# leduino.net
KiCad netlist of a schematic drawn in EAGLE
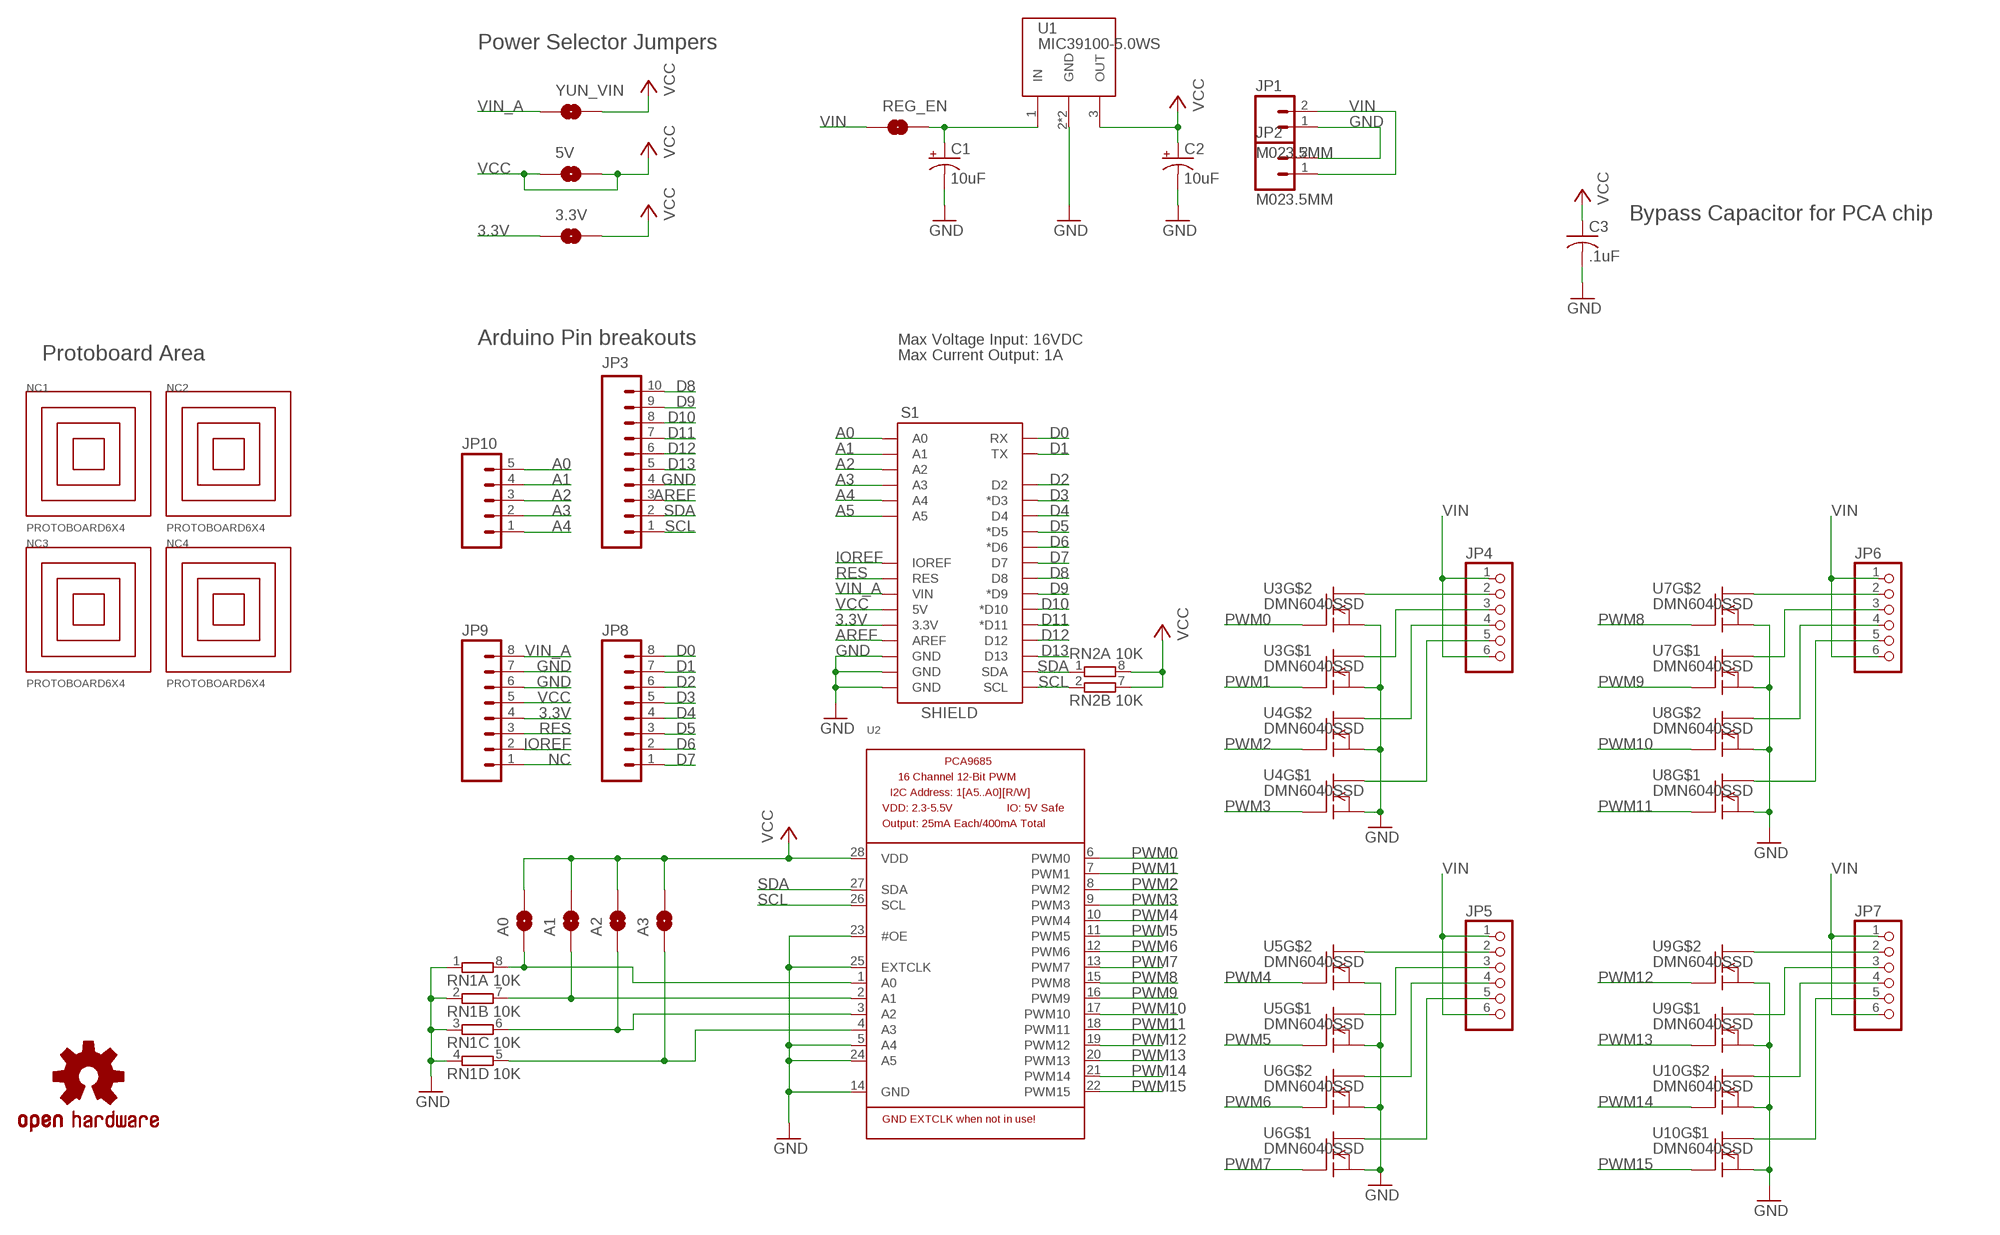
[diagram p0: schematic, sheet 1]

(export (version "E")
  (design (tool "Eeschema 10.0.6"))
  (components
    (comp (ref "3.3V")
      (value "SOLDERJUMPERNO")
      (footprint "eagle-import:SJ_2S-NO")
      (libsource (lib "eagle-import") (part "SOLDERJUMPERNO"))
    )
    (comp (ref "5V")
      (value "SOLDERJUMPERNO")
      (footprint "eagle-import:SJ_2S-NO")
      (libsource (lib "eagle-import") (part "SOLDERJUMPERNO"))
    )
    (comp (ref "A0")
      (value "SOLDERJUMPERNO")
      (footprint "eagle-import:SJ_2S-NO")
      (libsource (lib "eagle-import") (part "SOLDERJUMPERNO"))
    )
    (comp (ref "A1")
      (value "SOLDERJUMPERNO")
      (footprint "eagle-import:SJ_2S-NO")
      (libsource (lib "eagle-import") (part "SOLDERJUMPERNO"))
    )
    (comp (ref "A2")
      (value "SOLDERJUMPERNO")
      (footprint "eagle-import:SJ_2S-NO")
      (libsource (lib "eagle-import") (part "SOLDERJUMPERNO"))
    )
    (comp (ref "A3")
      (value "SOLDERJUMPERNO")
      (footprint "eagle-import:SJ_2S-NO")
      (libsource (lib "eagle-import") (part "SOLDERJUMPERNO"))
    )
    (comp (ref "C1")
      (value "10uF")
      (footprint "eagle-import:EIA3216")
      (libsource (lib "eagle-import") (part "CAP_POL1206"))
    )
    (comp (ref "C2")
      (value "10uF")
      (footprint "eagle-import:EIA3216")
      (libsource (lib "eagle-import") (part "CAP_POL1206"))
    )
    (comp (ref "C3")
      (value ".1uF")
      (footprint "eagle-import:C0805")
      (libsource (lib "eagle-import") (part "C-USC0805"))
    )
    (comp (ref "JP1")
      (value "M023.5MM")
      (footprint "eagle-import:SCREWTERMINAL-3.5MM-2")
      (libsource (lib "eagle-import") (part "M023.5MM"))
    )
    (comp (ref "JP2")
      (value "M023.5MM")
      (footprint "eagle-import:SCREWTERMINAL-3.5MM-2")
      (libsource (lib "eagle-import") (part "M023.5MM"))
    )
    (comp (ref "JP3")
      (value "M10NO_SILK_PTH_FEMALE")
      (footprint "eagle-import:1X10_NO_SILK")
      (libsource (lib "eagle-import") (part "M10NO_SILK_PTH_FEMALE"))
    )
    (comp (ref "JP4")
      (value "PINHD-1X63.5MM-RA")
      (footprint "eagle-import:1X06-3.5M-RA")
      (libsource (lib "eagle-import") (part "PINHD-1X63.5MM-RA"))
    )
    (comp (ref "JP5")
      (value "PINHD-1X63.5MM-RA")
      (footprint "eagle-import:1X06-3.5M-RA")
      (libsource (lib "eagle-import") (part "PINHD-1X63.5MM-RA"))
    )
    (comp (ref "JP6")
      (value "PINHD-1X63.5MM-RA")
      (footprint "eagle-import:1X06-3.5M-RA")
      (libsource (lib "eagle-import") (part "PINHD-1X63.5MM-RA"))
    )
    (comp (ref "JP7")
      (value "PINHD-1X63.5MM-RA")
      (footprint "eagle-import:1X06-3.5M-RA")
      (libsource (lib "eagle-import") (part "PINHD-1X63.5MM-RA"))
    )
    (comp (ref "JP8")
      (value "M08NO_SILK_FEMALE_PTH")
      (footprint "eagle-import:1X08_NO_SILK")
      (libsource (lib "eagle-import") (part "M08NO_SILK_FEMALE_PTH"))
    )
    (comp (ref "JP9")
      (value "M08NO_SILK_FEMALE_PTH")
      (footprint "eagle-import:1X08_NO_SILK")
      (libsource (lib "eagle-import") (part "M08NO_SILK_FEMALE_PTH"))
    )
    (comp (ref "JP10")
      (value "M05NO_SILK")
      (footprint "eagle-import:1X05_NO_SILK")
      (libsource (lib "eagle-import") (part "M05NO_SILK"))
    )
    (comp (ref "NC1")
      (value "PROTOBOARD6X4")
      (footprint "eagle-import:PROTOBOARD_6X4")
      (libsource (lib "eagle-import") (part "PROTOBOARD6X4"))
    )
    (comp (ref "NC2")
      (value "PROTOBOARD6X4")
      (footprint "eagle-import:PROTOBOARD_6X4")
      (libsource (lib "eagle-import") (part "PROTOBOARD6X4"))
    )
    (comp (ref "NC3")
      (value "PROTOBOARD6X4")
      (footprint "eagle-import:PROTOBOARD_6X4")
      (libsource (lib "eagle-import") (part "PROTOBOARD6X4"))
    )
    (comp (ref "NC4")
      (value "PROTOBOARD6X4")
      (footprint "eagle-import:PROTOBOARD_6X4")
      (libsource (lib "eagle-import") (part "PROTOBOARD6X4"))
    )
    (comp (ref "REG_EN")
      (value "SOLDERJUMPERNO")
      (footprint "eagle-import:SJ_2S-NO")
      (libsource (lib "eagle-import") (part "SOLDERJUMPERNO"))
    )
    (comp (ref "RN1")
      (value "10K")
      (footprint "eagle-import:EXB38V")
      (libsource (lib "eagle-import") (part "4R-NEXB38V"))
    )
    (comp (ref "RN2")
      (value "10K")
      (footprint "eagle-import:EXB38V")
      (libsource (lib "eagle-import") (part "4R-NEXB38V"))
    )
    (comp (ref "S1")
      (value "SHIELD")
      (footprint "eagle-import:ARDUINOR3")
      (libsource (lib "eagle-import") (part "ARDUINO_R3_SHIELD"))
    )
    (comp (ref "U$6")
      (value "OSHW-LOGOM")
      (footprint "eagle-import:OSHW-LOGO-M")
      (libsource (lib "eagle-import") (part "OSHW-LOGOM"))
    )
    (comp (ref "U1")
      (value "MIC39100-5.0WS")
      (footprint "eagle-import:SOT223")
      (libsource (lib "eagle-import") (part "MIC39100"))
    )
    (comp (ref "U2")
      (value "PCA9685")
      (footprint "eagle-import:TSSOP28")
      (libsource (lib "eagle-import") (part "PCA9685"))
    )
    (comp (ref "U3")
      (value "DMN6040SSD")
      (footprint "eagle-import:SO8")
      (libsource (lib "eagle-import") (part "DMN6040SSD"))
    )
    (comp (ref "U4")
      (value "DMN6040SSD")
      (footprint "eagle-import:SO8")
      (libsource (lib "eagle-import") (part "DMN6040SSD"))
    )
    (comp (ref "U5")
      (value "DMN6040SSD")
      (footprint "eagle-import:SO8")
      (libsource (lib "eagle-import") (part "DMN6040SSD"))
    )
    (comp (ref "U6")
      (value "DMN6040SSD")
      (footprint "eagle-import:SO8")
      (libsource (lib "eagle-import") (part "DMN6040SSD"))
    )
    (comp (ref "U7")
      (value "DMN6040SSD")
      (footprint "eagle-import:SO8")
      (libsource (lib "eagle-import") (part "DMN6040SSD"))
    )
    (comp (ref "U8")
      (value "DMN6040SSD")
      (footprint "eagle-import:SO8")
      (libsource (lib "eagle-import") (part "DMN6040SSD"))
    )
    (comp (ref "U9")
      (value "DMN6040SSD")
      (footprint "eagle-import:SO8")
      (libsource (lib "eagle-import") (part "DMN6040SSD"))
    )
    (comp (ref "U10")
      (value "DMN6040SSD")
      (footprint "eagle-import:SO8")
      (libsource (lib "eagle-import") (part "DMN6040SSD"))
    )
    (comp (ref "YUN_VIN")
      (value "SOLDERJUMPERNO")
      (footprint "eagle-import:SJ_2S-NO")
      (libsource (lib "eagle-import") (part "SOLDERJUMPERNO"))
    )
  )
  (nets
    (net (code "1") (name "/3.3V") (class "Default")
      (node (ref "3.3V") (pin "1") (pinfunction "1_1") (pintype "passive"))
      (node (ref "JP9") (pin "4") (pinfunction "4_4") (pintype "passive"))
      (node (ref "S1") (pin "3V") (pinfunction "3.3V_3V") (pintype "bidirectional"))
    )
    (net (code "2") (name "/A0") (class "Default")
      (node (ref "JP10") (pin "5") (pinfunction "5_5") (pintype "passive"))
      (node (ref "S1") (pin "A0") (pinfunction "A0_A0") (pintype "bidirectional"))
    )
    (net (code "3") (name "/A1") (class "Default")
      (node (ref "JP10") (pin "4") (pinfunction "4_4") (pintype "passive"))
      (node (ref "S1") (pin "A1") (pinfunction "A1_A1") (pintype "bidirectional"))
    )
    (net (code "4") (name "/A2") (class "Default")
      (node (ref "JP10") (pin "3") (pinfunction "3_3") (pintype "passive"))
      (node (ref "S1") (pin "A2") (pinfunction "A2_A2") (pintype "bidirectional"))
    )
    (net (code "5") (name "/A3") (class "Default")
      (node (ref "JP10") (pin "2") (pinfunction "2_2") (pintype "passive"))
      (node (ref "S1") (pin "A3") (pinfunction "A3_A3") (pintype "bidirectional"))
    )
    (net (code "6") (name "/A4") (class "Default")
      (node (ref "JP10") (pin "1") (pinfunction "1_1") (pintype "passive"))
      (node (ref "S1") (pin "A4") (pinfunction "A4_A4") (pintype "bidirectional"))
    )
    (net (code "7") (name "/A5") (class "Default")
      (node (ref "S1") (pin "A5") (pinfunction "A5_A5") (pintype "bidirectional"))
    )
    (net (code "8") (name "/AREF") (class "Default")
      (node (ref "JP3") (pin "3") (pinfunction "3_3") (pintype "passive"))
      (node (ref "S1") (pin "AREF") (pinfunction "AREF_AREF") (pintype "bidirectional"))
    )
    (net (code "9") (name "/D0") (class "Default")
      (node (ref "JP8") (pin "8") (pinfunction "8_8") (pintype "passive"))
      (node (ref "S1") (pin "D0") (pinfunction "RX_D0") (pintype "bidirectional"))
    )
    (net (code "10") (name "/D1") (class "Default")
      (node (ref "JP8") (pin "7") (pinfunction "7_7") (pintype "passive"))
      (node (ref "S1") (pin "D1") (pinfunction "TX_D1") (pintype "bidirectional"))
    )
    (net (code "11") (name "/D2") (class "Default")
      (node (ref "JP8") (pin "6") (pinfunction "6_6") (pintype "passive"))
      (node (ref "S1") (pin "D2") (pinfunction "D2_D2") (pintype "bidirectional"))
    )
    (net (code "12") (name "/D3") (class "Default")
      (node (ref "JP8") (pin "5") (pinfunction "5_5") (pintype "passive"))
      (node (ref "S1") (pin "D3") (pinfunction "*D3_D3") (pintype "bidirectional"))
    )
    (net (code "13") (name "/D4") (class "Default")
      (node (ref "JP8") (pin "4") (pinfunction "4_4") (pintype "passive"))
      (node (ref "S1") (pin "D4") (pinfunction "D4_D4") (pintype "bidirectional"))
    )
    (net (code "14") (name "/D5") (class "Default")
      (node (ref "JP8") (pin "3") (pinfunction "3_3") (pintype "passive"))
      (node (ref "S1") (pin "D5") (pinfunction "*D5_D5") (pintype "bidirectional"))
    )
    (net (code "15") (name "/D6") (class "Default")
      (node (ref "JP8") (pin "2") (pinfunction "2_2") (pintype "passive"))
      (node (ref "S1") (pin "D6") (pinfunction "*D6_D6") (pintype "bidirectional"))
    )
    (net (code "16") (name "/D7") (class "Default")
      (node (ref "JP8") (pin "1") (pinfunction "1_1") (pintype "passive"))
      (node (ref "S1") (pin "D7") (pinfunction "D7_D7") (pintype "bidirectional"))
    )
    (net (code "17") (name "/D8") (class "Default")
      (node (ref "JP3") (pin "10") (pinfunction "10_10") (pintype "passive"))
      (node (ref "S1") (pin "D8") (pinfunction "D8_D8") (pintype "bidirectional"))
    )
    (net (code "18") (name "/D9") (class "Default")
      (node (ref "JP3") (pin "9") (pinfunction "9_9") (pintype "passive"))
      (node (ref "S1") (pin "D9") (pinfunction "*D9_D9") (pintype "bidirectional"))
    )
    (net (code "19") (name "/D10") (class "Default")
      (node (ref "JP3") (pin "8") (pinfunction "8_8") (pintype "passive"))
      (node (ref "S1") (pin "D10") (pinfunction "*D10_D10") (pintype "bidirectional"))
    )
    (net (code "20") (name "/D11") (class "Default")
      (node (ref "JP3") (pin "7") (pinfunction "7_7") (pintype "passive"))
      (node (ref "S1") (pin "D11") (pinfunction "*D11_D11") (pintype "bidirectional"))
    )
    (net (code "21") (name "/D12") (class "Default")
      (node (ref "JP3") (pin "6") (pinfunction "6_6") (pintype "passive"))
      (node (ref "S1") (pin "D12") (pinfunction "D12_D12") (pintype "bidirectional"))
    )
    (net (code "22") (name "/D13") (class "Default")
      (node (ref "JP3") (pin "5") (pinfunction "5_5") (pintype "passive"))
      (node (ref "S1") (pin "D13") (pinfunction "D13_D13") (pintype "bidirectional"))
    )
    (net (code "23") (name "/IOREF") (class "Default")
      (node (ref "JP9") (pin "2") (pinfunction "2_2") (pintype "passive"))
      (node (ref "S1") (pin "IOREF") (pinfunction "IOREF_IOREF") (pintype "bidirectional"))
    )
    (net (code "24") (name "/NC") (class "Default")
      (node (ref "JP9") (pin "1") (pinfunction "1_1") (pintype "passive"))
    )
    (net (code "25") (name "/PWM0") (class "Default")
      (node (ref "U2") (pin "6") (pinfunction "PWM0_6") (pintype "output"))
      (node (ref "U3") (pin "4") (pinfunction "G_4") (pintype "passive"))
    )
    (net (code "26") (name "/PWM1") (class "Default")
      (node (ref "U2") (pin "7") (pinfunction "PWM1_7") (pintype "output"))
      (node (ref "U3") (pin "2") (pinfunction "G_2") (pintype "passive"))
    )
    (net (code "27") (name "/PWM2") (class "Default")
      (node (ref "U2") (pin "8") (pinfunction "PWM2_8") (pintype "output"))
      (node (ref "U4") (pin "4") (pinfunction "G_4") (pintype "passive"))
    )
    (net (code "28") (name "/PWM3") (class "Default")
      (node (ref "U2") (pin "9") (pinfunction "PWM3_9") (pintype "output"))
      (node (ref "U4") (pin "2") (pinfunction "G_2") (pintype "passive"))
    )
    (net (code "29") (name "/PWM4") (class "Default")
      (node (ref "U2") (pin "10") (pinfunction "PWM4_10") (pintype "output"))
      (node (ref "U5") (pin "4") (pinfunction "G_4") (pintype "passive"))
    )
    (net (code "30") (name "/PWM5") (class "Default")
      (node (ref "U2") (pin "11") (pinfunction "PWM5_11") (pintype "output"))
      (node (ref "U5") (pin "2") (pinfunction "G_2") (pintype "passive"))
    )
    (net (code "31") (name "/PWM6") (class "Default")
      (node (ref "U2") (pin "12") (pinfunction "PWM6_12") (pintype "output"))
      (node (ref "U6") (pin "4") (pinfunction "G_4") (pintype "passive"))
    )
    (net (code "32") (name "/PWM7") (class "Default")
      (node (ref "U2") (pin "13") (pinfunction "PWM7_13") (pintype "output"))
      (node (ref "U6") (pin "2") (pinfunction "G_2") (pintype "passive"))
    )
    (net (code "33") (name "/PWM8") (class "Default")
      (node (ref "U2") (pin "15") (pinfunction "PWM8_15") (pintype "output"))
      (node (ref "U7") (pin "4") (pinfunction "G_4") (pintype "passive"))
    )
    (net (code "34") (name "/PWM9") (class "Default")
      (node (ref "U2") (pin "16") (pinfunction "PWM9_16") (pintype "output"))
      (node (ref "U7") (pin "2") (pinfunction "G_2") (pintype "passive"))
    )
    (net (code "35") (name "/PWM10") (class "Default")
      (node (ref "U2") (pin "17") (pinfunction "PWM10_17") (pintype "output"))
      (node (ref "U8") (pin "4") (pinfunction "G_4") (pintype "passive"))
    )
    (net (code "36") (name "/PWM11") (class "Default")
      (node (ref "U2") (pin "18") (pinfunction "PWM11_18") (pintype "output"))
      (node (ref "U8") (pin "2") (pinfunction "G_2") (pintype "passive"))
    )
    (net (code "37") (name "/PWM12") (class "Default")
      (node (ref "U2") (pin "19") (pinfunction "PWM12_19") (pintype "output"))
      (node (ref "U9") (pin "4") (pinfunction "G_4") (pintype "passive"))
    )
    (net (code "38") (name "/PWM13") (class "Default")
      (node (ref "U2") (pin "20") (pinfunction "PWM13_20") (pintype "output"))
      (node (ref "U9") (pin "2") (pinfunction "G_2") (pintype "passive"))
    )
    (net (code "39") (name "/PWM14") (class "Default")
      (node (ref "U10") (pin "4") (pinfunction "G_4") (pintype "passive"))
      (node (ref "U2") (pin "21") (pinfunction "PWM14_21") (pintype "output"))
    )
    (net (code "40") (name "/PWM15") (class "Default")
      (node (ref "U10") (pin "2") (pinfunction "G_2") (pintype "passive"))
      (node (ref "U2") (pin "22") (pinfunction "PWM15_22") (pintype "output"))
    )
    (net (code "41") (name "/RES") (class "Default")
      (node (ref "JP9") (pin "3") (pinfunction "3_3") (pintype "passive"))
      (node (ref "S1") (pin "RESET") (pinfunction "RES_RESET") (pintype "bidirectional"))
    )
    (net (code "42") (name "/SCL") (class "Default")
      (node (ref "JP3") (pin "1") (pinfunction "1_1") (pintype "passive"))
      (node (ref "RN2") (pin "2") (pinfunction "1_2") (pintype "passive"))
      (node (ref "S1") (pin "SCL") (pinfunction "SCL_SCL") (pintype "bidirectional"))
      (node (ref "U2") (pin "26") (pinfunction "SCL_26") (pintype "bidirectional"))
    )
    (net (code "43") (name "/SDA") (class "Default")
      (node (ref "JP3") (pin "2") (pinfunction "2_2") (pintype "passive"))
      (node (ref "RN2") (pin "1") (pinfunction "1_1") (pintype "passive"))
      (node (ref "S1") (pin "SDA") (pinfunction "SDA_SDA") (pintype "bidirectional"))
      (node (ref "U2") (pin "27") (pinfunction "SDA_27") (pintype "bidirectional"))
    )
    (net (code "44") (name "/VIN") (class "Default")
      (node (ref "JP1") (pin "2") (pinfunction "2_2") (pintype "passive"))
      (node (ref "JP2") (pin "1") (pinfunction "1_1") (pintype "passive"))
      (node (ref "JP4") (pin "1") (pinfunction "1_1") (pintype "passive"))
      (node (ref "JP4") (pin "6") (pinfunction "6_6") (pintype "passive"))
      (node (ref "JP5") (pin "1") (pinfunction "1_1") (pintype "passive"))
      (node (ref "JP5") (pin "6") (pinfunction "6_6") (pintype "passive"))
      (node (ref "JP6") (pin "1") (pinfunction "1_1") (pintype "passive"))
      (node (ref "JP6") (pin "6") (pinfunction "6_6") (pintype "passive"))
      (node (ref "JP7") (pin "1") (pinfunction "1_1") (pintype "passive"))
      (node (ref "JP7") (pin "6") (pinfunction "6_6") (pintype "passive"))
      (node (ref "REG_EN") (pin "1") (pinfunction "1_1") (pintype "passive"))
    )
    (net (code "45") (name "/VIN_A") (class "Default")
      (node (ref "JP9") (pin "8") (pinfunction "8_8") (pintype "passive"))
      (node (ref "S1") (pin "VIN") (pinfunction "VIN_VIN") (pintype "bidirectional"))
      (node (ref "YUN_VIN") (pin "1") (pinfunction "1_1") (pintype "passive"))
    )
    (net (code "46") (name "GND") (class "Default")
      (node (ref "C1") (pin "C") (pinfunction "-_C") (pintype "passive"))
      (node (ref "C2") (pin "C") (pinfunction "-_C") (pintype "passive"))
      (node (ref "C3") (pin "2") (pinfunction "2_2") (pintype "passive"))
      (node (ref "JP1") (pin "1") (pinfunction "1_1") (pintype "passive"))
      (node (ref "JP2") (pin "2") (pinfunction "2_2") (pintype "passive"))
      (node (ref "JP3") (pin "4") (pinfunction "4_4") (pintype "passive"))
      (node (ref "JP9") (pin "6") (pinfunction "6_6") (pintype "passive"))
      (node (ref "JP9") (pin "7") (pinfunction "7_7") (pintype "passive"))
      (node (ref "RN1") (pin "1") (pinfunction "1_1") (pintype "passive"))
      (node (ref "RN1") (pin "2") (pinfunction "1_2") (pintype "passive"))
      (node (ref "RN1") (pin "3") (pinfunction "1_3") (pintype "passive"))
      (node (ref "RN1") (pin "4") (pinfunction "1_4") (pintype "passive"))
      (node (ref "S1") (pin "GND") (pinfunction "GND_GND") (pintype "bidirectional"))
      (node (ref "S1") (pin "GND1") (pinfunction "GND_GND1") (pintype "bidirectional"))
      (node (ref "S1") (pin "GND2") (pinfunction "GND_GND2") (pintype "bidirectional"))
      (node (ref "U1") (pin "2") (pinfunction "GND_2") (pintype "input"))
      (node (ref "U1") (pin "4") (pinfunction "GND_4") (pintype "input"))
      (node (ref "U10") (pin "1") (pinfunction "S_1") (pintype "passive"))
      (node (ref "U10") (pin "3") (pinfunction "S_3") (pintype "passive"))
      (node (ref "U2") (pin "14") (pinfunction "GND_14") (pintype "power_in"))
      (node (ref "U2") (pin "23") (pinfunction "#OE_23") (pintype "input"))
      (node (ref "U2") (pin "24") (pinfunction "A5_24") (pintype "bidirectional"))
      (node (ref "U2") (pin "25") (pinfunction "EXTCLK_25") (pintype "input"))
      (node (ref "U2") (pin "5") (pinfunction "A4_5") (pintype "bidirectional"))
      (node (ref "U3") (pin "1") (pinfunction "S_1") (pintype "passive"))
      (node (ref "U3") (pin "3") (pinfunction "S_3") (pintype "passive"))
      (node (ref "U4") (pin "1") (pinfunction "S_1") (pintype "passive"))
      (node (ref "U4") (pin "3") (pinfunction "S_3") (pintype "passive"))
      (node (ref "U5") (pin "1") (pinfunction "S_1") (pintype "passive"))
      (node (ref "U5") (pin "3") (pinfunction "S_3") (pintype "passive"))
      (node (ref "U6") (pin "1") (pinfunction "S_1") (pintype "passive"))
      (node (ref "U6") (pin "3") (pinfunction "S_3") (pintype "passive"))
      (node (ref "U7") (pin "1") (pinfunction "S_1") (pintype "passive"))
      (node (ref "U7") (pin "3") (pinfunction "S_3") (pintype "passive"))
      (node (ref "U8") (pin "1") (pinfunction "S_1") (pintype "passive"))
      (node (ref "U8") (pin "3") (pinfunction "S_3") (pintype "passive"))
      (node (ref "U9") (pin "1") (pinfunction "S_1") (pintype "passive"))
      (node (ref "U9") (pin "3") (pinfunction "S_3") (pintype "passive"))
    )
    (net (code "47") (name "Net-(C1-+)") (class "Default")
      (node (ref "C1") (pin "A") (pinfunction "+_A") (pintype "passive"))
      (node (ref "REG_EN") (pin "2") (pinfunction "2_2") (pintype "passive"))
      (node (ref "U1") (pin "1") (pinfunction "IN_1") (pintype "input"))
    )
    (net (code "48") (name "Net-(JP4-Pad2)") (class "Default")
      (node (ref "JP4") (pin "2") (pinfunction "2_2") (pintype "passive"))
      (node (ref "U3") (pin "5") (pinfunction "D_5") (pintype "passive"))
      (node (ref "U3") (pin "6") (pinfunction "D_6") (pintype "passive"))
    )
    (net (code "49") (name "Net-(JP4-Pad3)") (class "Default")
      (node (ref "JP4") (pin "3") (pinfunction "3_3") (pintype "passive"))
      (node (ref "U3") (pin "7") (pinfunction "D_7") (pintype "passive"))
      (node (ref "U3") (pin "8") (pinfunction "D_8") (pintype "passive"))
    )
    (net (code "50") (name "Net-(JP4-Pad4)") (class "Default")
      (node (ref "JP4") (pin "4") (pinfunction "4_4") (pintype "passive"))
      (node (ref "U4") (pin "5") (pinfunction "D_5") (pintype "passive"))
      (node (ref "U4") (pin "6") (pinfunction "D_6") (pintype "passive"))
    )
    (net (code "51") (name "Net-(JP4-Pad5)") (class "Default")
      (node (ref "JP4") (pin "5") (pinfunction "5_5") (pintype "passive"))
      (node (ref "U4") (pin "7") (pinfunction "D_7") (pintype "passive"))
      (node (ref "U4") (pin "8") (pinfunction "D_8") (pintype "passive"))
    )
    (net (code "52") (name "Net-(JP5-Pad2)") (class "Default")
      (node (ref "JP5") (pin "2") (pinfunction "2_2") (pintype "passive"))
      (node (ref "U5") (pin "5") (pinfunction "D_5") (pintype "passive"))
      (node (ref "U5") (pin "6") (pinfunction "D_6") (pintype "passive"))
    )
    (net (code "53") (name "Net-(JP5-Pad3)") (class "Default")
      (node (ref "JP5") (pin "3") (pinfunction "3_3") (pintype "passive"))
      (node (ref "U5") (pin "7") (pinfunction "D_7") (pintype "passive"))
      (node (ref "U5") (pin "8") (pinfunction "D_8") (pintype "passive"))
    )
    (net (code "54") (name "Net-(JP5-Pad4)") (class "Default")
      (node (ref "JP5") (pin "4") (pinfunction "4_4") (pintype "passive"))
      (node (ref "U6") (pin "5") (pinfunction "D_5") (pintype "passive"))
      (node (ref "U6") (pin "6") (pinfunction "D_6") (pintype "passive"))
    )
    (net (code "55") (name "Net-(JP5-Pad5)") (class "Default")
      (node (ref "JP5") (pin "5") (pinfunction "5_5") (pintype "passive"))
      (node (ref "U6") (pin "7") (pinfunction "D_7") (pintype "passive"))
      (node (ref "U6") (pin "8") (pinfunction "D_8") (pintype "passive"))
    )
    (net (code "56") (name "Net-(JP6-Pad2)") (class "Default")
      (node (ref "JP6") (pin "2") (pinfunction "2_2") (pintype "passive"))
      (node (ref "U7") (pin "5") (pinfunction "D_5") (pintype "passive"))
      (node (ref "U7") (pin "6") (pinfunction "D_6") (pintype "passive"))
    )
    (net (code "57") (name "Net-(JP6-Pad3)") (class "Default")
      (node (ref "JP6") (pin "3") (pinfunction "3_3") (pintype "passive"))
      (node (ref "U7") (pin "7") (pinfunction "D_7") (pintype "passive"))
      (node (ref "U7") (pin "8") (pinfunction "D_8") (pintype "passive"))
    )
    (net (code "58") (name "Net-(JP6-Pad4)") (class "Default")
      (node (ref "JP6") (pin "4") (pinfunction "4_4") (pintype "passive"))
      (node (ref "U8") (pin "5") (pinfunction "D_5") (pintype "passive"))
      (node (ref "U8") (pin "6") (pinfunction "D_6") (pintype "passive"))
    )
    (net (code "59") (name "Net-(JP6-Pad5)") (class "Default")
      (node (ref "JP6") (pin "5") (pinfunction "5_5") (pintype "passive"))
      (node (ref "U8") (pin "7") (pinfunction "D_7") (pintype "passive"))
      (node (ref "U8") (pin "8") (pinfunction "D_8") (pintype "passive"))
    )
    (net (code "60") (name "Net-(JP7-Pad2)") (class "Default")
      (node (ref "JP7") (pin "2") (pinfunction "2_2") (pintype "passive"))
      (node (ref "U9") (pin "5") (pinfunction "D_5") (pintype "passive"))
      (node (ref "U9") (pin "6") (pinfunction "D_6") (pintype "passive"))
    )
    (net (code "61") (name "Net-(JP7-Pad3)") (class "Default")
      (node (ref "JP7") (pin "3") (pinfunction "3_3") (pintype "passive"))
      (node (ref "U9") (pin "7") (pinfunction "D_7") (pintype "passive"))
      (node (ref "U9") (pin "8") (pinfunction "D_8") (pintype "passive"))
    )
    (net (code "62") (name "Net-(JP7-Pad4)") (class "Default")
      (node (ref "JP7") (pin "4") (pinfunction "4_4") (pintype "passive"))
      (node (ref "U10") (pin "5") (pinfunction "D_5") (pintype "passive"))
      (node (ref "U10") (pin "6") (pinfunction "D_6") (pintype "passive"))
    )
    (net (code "63") (name "Net-(JP7-Pad5)") (class "Default")
      (node (ref "JP7") (pin "5") (pinfunction "5_5") (pintype "passive"))
      (node (ref "U10") (pin "7") (pinfunction "D_7") (pintype "passive"))
      (node (ref "U10") (pin "8") (pinfunction "D_8") (pintype "passive"))
    )
    (net (code "64") (name "Net-(RN1A-2)") (class "Default")
      (node (ref "A0") (pin "1") (pinfunction "1_1") (pintype "passive"))
      (node (ref "RN1") (pin "8") (pinfunction "2_8") (pintype "passive"))
      (node (ref "U2") (pin "1") (pinfunction "A0_1") (pintype "bidirectional"))
    )
    (net (code "65") (name "Net-(RN1B-2)") (class "Default")
      (node (ref "A1") (pin "1") (pinfunction "1_1") (pintype "passive"))
      (node (ref "RN1") (pin "7") (pinfunction "2_7") (pintype "passive"))
      (node (ref "U2") (pin "2") (pinfunction "A1_2") (pintype "bidirectional"))
    )
    (net (code "66") (name "Net-(RN1C-2)") (class "Default")
      (node (ref "A2") (pin "1") (pinfunction "1_1") (pintype "passive"))
      (node (ref "RN1") (pin "6") (pinfunction "2_6") (pintype "passive"))
      (node (ref "U2") (pin "3") (pinfunction "A2_3") (pintype "bidirectional"))
    )
    (net (code "67") (name "Net-(RN1D-2)") (class "Default")
      (node (ref "A3") (pin "1") (pinfunction "1_1") (pintype "passive"))
      (node (ref "RN1") (pin "5") (pinfunction "2_5") (pintype "passive"))
      (node (ref "U2") (pin "4") (pinfunction "A3_4") (pintype "bidirectional"))
    )
    (net (code "68") (name "VCC") (class "Default")
      (node (ref "3.3V") (pin "2") (pinfunction "2_2") (pintype "passive"))
      (node (ref "5V") (pin "1") (pinfunction "1_1") (pintype "passive"))
      (node (ref "5V") (pin "2") (pinfunction "2_2") (pintype "passive"))
      (node (ref "A0") (pin "2") (pinfunction "2_2") (pintype "passive"))
      (node (ref "A1") (pin "2") (pinfunction "2_2") (pintype "passive"))
      (node (ref "A2") (pin "2") (pinfunction "2_2") (pintype "passive"))
      (node (ref "A3") (pin "2") (pinfunction "2_2") (pintype "passive"))
      (node (ref "C2") (pin "A") (pinfunction "+_A") (pintype "passive"))
      (node (ref "C3") (pin "1") (pinfunction "1_1") (pintype "passive"))
      (node (ref "JP9") (pin "5") (pinfunction "5_5") (pintype "passive"))
      (node (ref "RN2") (pin "7") (pinfunction "2_7") (pintype "passive"))
      (node (ref "RN2") (pin "8") (pinfunction "2_8") (pintype "passive"))
      (node (ref "S1") (pin "5V") (pinfunction "5V_5V") (pintype "bidirectional"))
      (node (ref "U1") (pin "3") (pinfunction "OUT_3") (pintype "output"))
      (node (ref "U2") (pin "28") (pinfunction "VDD_28") (pintype "power_in"))
      (node (ref "YUN_VIN") (pin "2") (pinfunction "2_2") (pintype "passive"))
    )
  )
)
